# Power_Circuit.net
KiCad netlist of a schematic drawn in Altium Designer
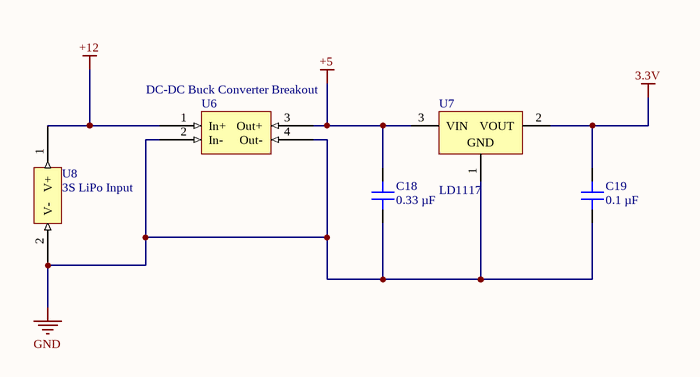
[diagram p0: Power_Circuit.SchDoc]

(export (version "E")
  (design (tool "Eeschema 10.0.6"))
  (components
    (comp (ref "C18")
      (value "0.33 µF")
      (footprint "CAP 1210_3225 - 1MM")
      (description "CAP CER 0.33UF 25V X7R 1210")
      (fields (field (name "PART NUMBER") "C1210C334J3RAC7800") (field (name "MANUFACTURER") "KEMET"))
      (libsource (lib "Celestial Altium Library - altium_library") (part "Capacitor"))
    )
    (comp (ref "C19")
      (value "0.1 µF")
      (footprint "CAP 1210_3225 - 1MM")
      (description "CAP CER 0.1UF 50V C0G/NP0 1210")
      (fields (field (name "PART NUMBER") "C1210C104J5GACAUTO") (field (name "MANUFACTURER") "KEMET"))
      (libsource (lib "Celestial Altium Library - altium_library") (part "Capacitor"))
    )
    (comp (ref "U6")
      (value "DC-DC Buck Converter Breakout")
      (footprint "DC-DC Buck Converter Breakout-Footprint-1")
      (libsource (lib "Donados") (part "New symbol 1"))
    )
    (comp (ref "U7")
      (value "LD1117")
      (footprint "PCB - LEADED - TO - TO-220")
      (description "Linear Voltage Regulator IC  1 Output  1A TO-220AB")
      (fields (field (name "ROWAN PART NUMBER") "776") (field (name "MANUFACTURER") "STMicroelectronics"))
      (libsource (lib "RowanAltiumLibrary") (part "SCH - POWER - LINEAR VREG - LD1117"))
    )
    (comp (ref "U8")
      (value "3S LiPo Input")
      (footprint "3S LiPo Input-Footprint-2")
      (libsource (lib "") (part "New symbol 1_1"))
    )
  )
  (nets
    (net (code "1") (name "+5") (class "Default")
      (node (ref "C18") (pin "2") (pinfunction "2_2") (pintype "passive"))
      (node (ref "U6") (pin "3") (pinfunction "Out+_3") (pintype "input"))
      (node (ref "U7") (pin "3") (pinfunction "VIN_3") (pintype "power_in"))
    )
    (net (code "2") (name "+12") (class "Default")
      (node (ref "U6") (pin "1") (pinfunction "In+_1") (pintype "input"))
      (node (ref "U8") (pin "1") (pinfunction "V+_1") (pintype "output"))
    )
    (net (code "3") (name "3.3V") (class "Default")
      (node (ref "C19") (pin "2") (pinfunction "2_2") (pintype "passive"))
      (node (ref "U7") (pin "2") (pinfunction "VOUT_2") (pintype "power_in"))
    )
    (net (code "4") (name "GND") (class "Default")
      (node (ref "C18") (pin "1") (pinfunction "1_1") (pintype "passive"))
      (node (ref "C19") (pin "1") (pinfunction "1_1") (pintype "passive"))
      (node (ref "U6") (pin "2") (pinfunction "In-_2") (pintype "input"))
      (node (ref "U6") (pin "4") (pinfunction "Out-_4") (pintype "input"))
      (node (ref "U7") (pin "1") (pinfunction "GND_1") (pintype "power_in"))
      (node (ref "U8") (pin "2") (pinfunction "V-_2") (pintype "input"))
    )
  )
)
